# LSM6DSMTR.net
KiCad netlist of a schematic drawn in Altium Designer
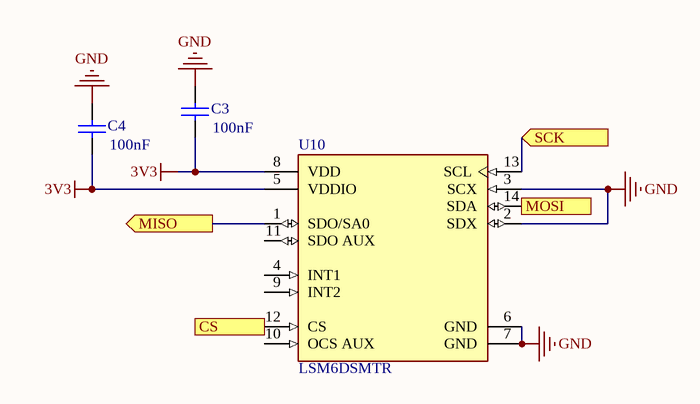
[diagram p0: LSM6DSMTR.SchDoc]

(export (version "E")
  (design (tool "Eeschema 10.0.6"))
  (components
    (comp (ref "C3")
      (value "100nF")
      (footprint "1608[0603]")
      (description "Capacitor")
      (fields (field (name "Comment") "Cap") (field (name "PUBLISHER") "Altium Limited"))
      (libsource (lib "Miscellaneous Devices") (part "Cap"))
    )
    (comp (ref "C4")
      (value "100nF")
      (footprint "1608[0603]")
      (description "Capacitor")
      (fields (field (name "Comment") "Cap") (field (name "PUBLISHER") "Altium Limited"))
      (libsource (lib "Miscellaneous Devices") (part "Cap"))
    )
    (comp (ref "U10")
      (value "LSM6DSMTR")
      (footprint "FP-LGA-14L-DM00249496-MFG")
      (description "IMU ACCEL/GYRO I2C/SPI 14LGA")
      (fields
        (field (name "OCTOPART") "https://octopart.com/lsm6dsmtr-stmicroelectronics-66358194")
        (field (name "MANUFACTURER") "STMicroelectronics")
      )
      (libsource (lib "Altium Content Vault") (part "dd82ae232bae541fa9c740d21cb9072"))
    )
  )
  (nets
    (net (code "1") (name "/CS") (class "Default")
      (node (ref "U10") (pin "12") (pinfunction "CS_12") (pintype "input"))
    )
    (net (code "2") (name "/MISO") (class "Default")
      (node (ref "U10") (pin "1") (pinfunction "SDO/SA0_1") (pintype "bidirectional"))
    )
    (net (code "3") (name "/MOSI") (class "Default")
      (node (ref "U10") (pin "14") (pinfunction "SDA_14") (pintype "bidirectional"))
    )
    (net (code "4") (name "/SCK") (class "Default")
      (node (ref "U10") (pin "13") (pinfunction "SCL_13") (pintype "input"))
    )
    (net (code "5") (name "3V3") (class "Default")
      (node (ref "C3") (pin "2") (pinfunction "2_2") (pintype "passive"))
      (node (ref "C4") (pin "2") (pinfunction "2_2") (pintype "passive"))
      (node (ref "U10") (pin "5") (pinfunction "VDDIO_5") (pintype "power_in"))
      (node (ref "U10") (pin "8") (pinfunction "VDD_8") (pintype "power_in"))
    )
    (net (code "6") (name "GND") (class "Default")
      (node (ref "C3") (pin "1") (pinfunction "1_1") (pintype "passive"))
      (node (ref "C4") (pin "1") (pinfunction "1_1") (pintype "passive"))
      (node (ref "U10") (pin "2") (pinfunction "SDX_2") (pintype "bidirectional"))
      (node (ref "U10") (pin "3") (pinfunction "SCX_3") (pintype "input"))
      (node (ref "U10") (pin "6") (pinfunction "GND_6") (pintype "power_in"))
      (node (ref "U10") (pin "7") (pinfunction "GND_7") (pintype "power_in"))
    )
    (net (code "7") (name "unconnected-(U10-INT1-Pad4)") (class "Default")
      (node (ref "U10") (pin "4") (pinfunction "INT1_4") (pintype "input"))
    )
    (net (code "8") (name "unconnected-(U10-INT2-Pad9)") (class "Default")
      (node (ref "U10") (pin "9") (pinfunction "INT2_9") (pintype "input"))
    )
    (net (code "9") (name "unconnected-(U10-OCS_AUX-Pad10)") (class "Default")
      (node (ref "U10") (pin "10") (pinfunction "OCS_AUX_10") (pintype "input"))
    )
    (net (code "10") (name "unconnected-(U10-SDO_AUX-Pad11)") (class "Default")
      (node (ref "U10") (pin "11") (pinfunction "SDO_AUX_11") (pintype "bidirectional"))
    )
  )
)
